# power.net
KiCad netlist of a schematic drawn in Altium Designer
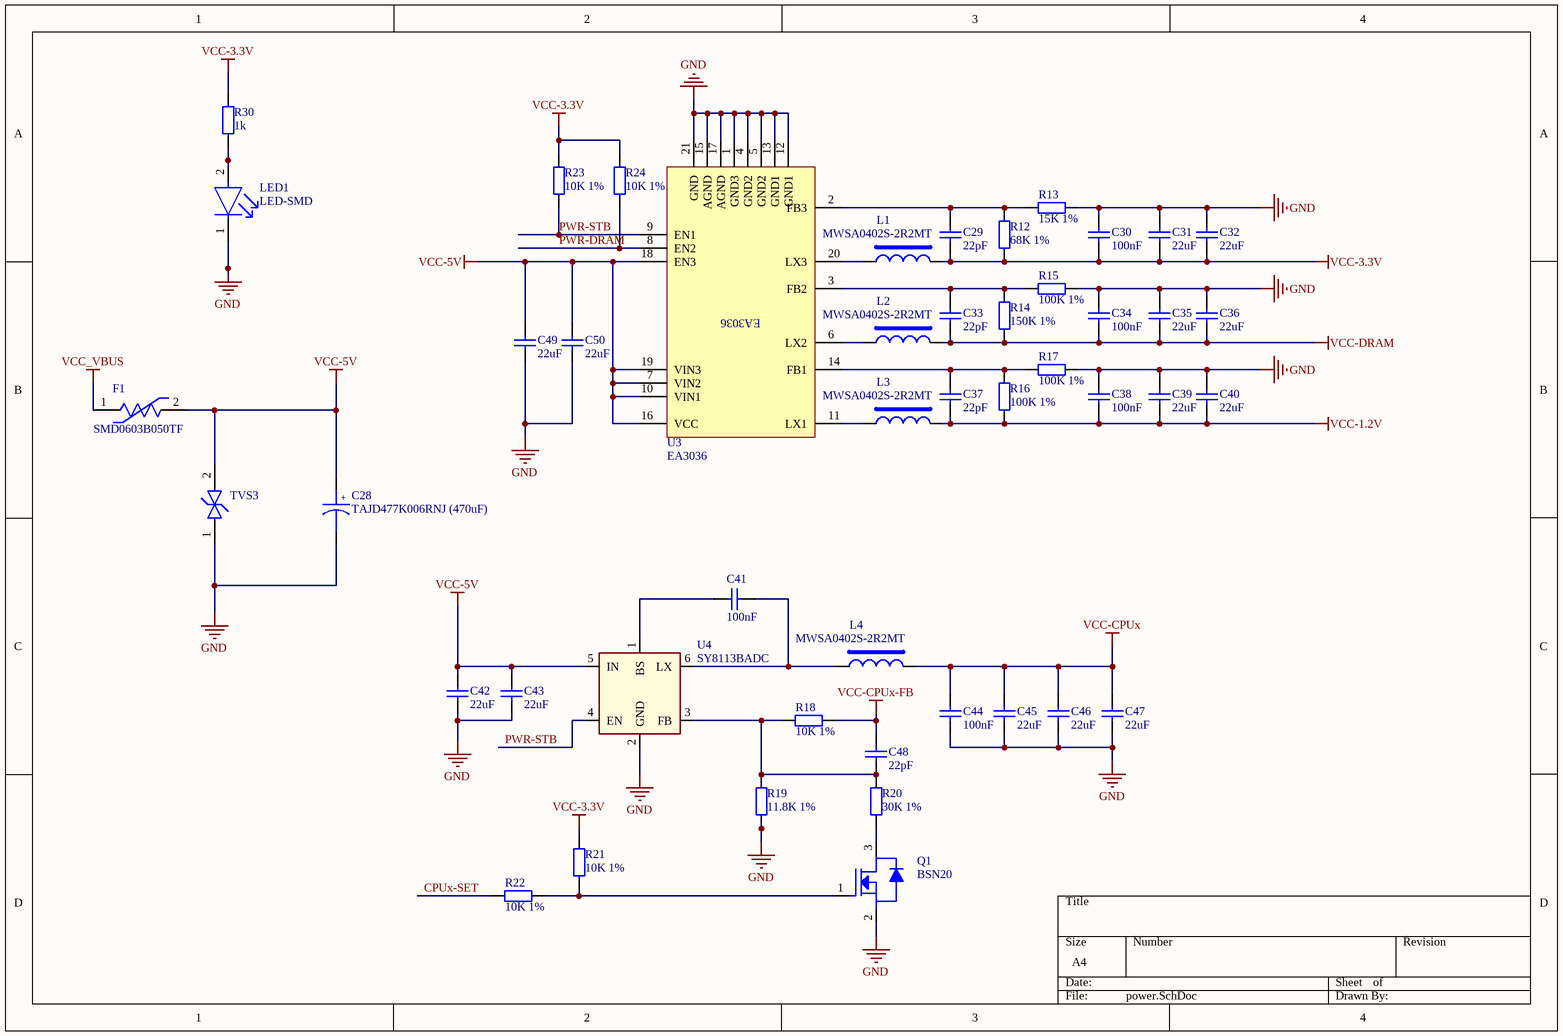
[diagram p0: power.SchDoc]

(export (version "E")
  (design (tool "Eeschema 10.0.6"))
  (components
    (comp (ref "C28")
      (value "TAJD477K006RNJ (470uF)")
      (footprint "7343_C_POL")
      (description "smd pol capacitor")
      (libsource (lib "Schlib") (part "CAP-POL-SMD"))
    )
    (comp (ref "C29")
      (value "22pF")
      (footprint "0402_C")
      (description "smd capacitor")
      (libsource (lib "Schlib") (part "CAP-SMD"))
    )
    (comp (ref "C30")
      (value "100nF")
      (footprint "0402_C")
      (description "smd capacitor")
      (libsource (lib "Schlib") (part "CAP-SMD"))
    )
    (comp (ref "C31")
      (value "22uF")
      (footprint "0603_C")
      (description "smd capacitor")
      (libsource (lib "Schlib") (part "CAP-SMD"))
    )
    (comp (ref "C32")
      (value "22uF")
      (footprint "0603_C")
      (description "smd capacitor")
      (libsource (lib "Schlib") (part "CAP-SMD"))
    )
    (comp (ref "C33")
      (value "22pF")
      (footprint "0402_C")
      (description "smd capacitor")
      (libsource (lib "Schlib") (part "CAP-SMD"))
    )
    (comp (ref "C34")
      (value "100nF")
      (footprint "0402_C")
      (description "smd capacitor")
      (libsource (lib "Schlib") (part "CAP-SMD"))
    )
    (comp (ref "C35")
      (value "22uF")
      (footprint "0603_C")
      (description "smd capacitor")
      (libsource (lib "Schlib") (part "CAP-SMD"))
    )
    (comp (ref "C36")
      (value "22uF")
      (footprint "0603_C")
      (description "smd capacitor")
      (libsource (lib "Schlib") (part "CAP-SMD"))
    )
    (comp (ref "C37")
      (value "22pF")
      (footprint "0402_C")
      (description "smd capacitor")
      (libsource (lib "Schlib") (part "CAP-SMD"))
    )
    (comp (ref "C38")
      (value "100nF")
      (footprint "0402_C")
      (description "smd capacitor")
      (libsource (lib "Schlib") (part "CAP-SMD"))
    )
    (comp (ref "C39")
      (value "22uF")
      (footprint "0603_C")
      (description "smd capacitor")
      (libsource (lib "Schlib") (part "CAP-SMD"))
    )
    (comp (ref "C40")
      (value "22uF")
      (footprint "0603_C")
      (description "smd capacitor")
      (libsource (lib "Schlib") (part "CAP-SMD"))
    )
    (comp (ref "C41")
      (value "100nF")
      (footprint "0402_C")
      (description "smd capacitor")
      (libsource (lib "Schlib") (part "CAP-SMD"))
    )
    (comp (ref "C42")
      (value "22uF")
      (footprint "0603_C")
      (description "smd capacitor")
      (libsource (lib "Schlib") (part "CAP-SMD"))
    )
    (comp (ref "C43")
      (value "22uF")
      (footprint "0603_C")
      (description "smd capacitor")
      (libsource (lib "Schlib") (part "CAP-SMD"))
    )
    (comp (ref "C44")
      (value "100nF")
      (footprint "0402_C")
      (description "smd capacitor")
      (libsource (lib "Schlib") (part "CAP-SMD"))
    )
    (comp (ref "C45")
      (value "22uF")
      (footprint "0603_C")
      (description "smd capacitor")
      (libsource (lib "Schlib") (part "CAP-SMD"))
    )
    (comp (ref "C46")
      (value "22uF")
      (footprint "0603_C")
      (description "smd capacitor")
      (libsource (lib "Schlib") (part "CAP-SMD"))
    )
    (comp (ref "C47")
      (value "22uF")
      (footprint "0603_C")
      (description "smd capacitor")
      (libsource (lib "Schlib") (part "CAP-SMD"))
    )
    (comp (ref "C48")
      (value "22pF")
      (footprint "0402_C")
      (description "smd capacitor")
      (libsource (lib "Schlib") (part "CAP-SMD"))
    )
    (comp (ref "C49")
      (value "22uF")
      (footprint "0603_C")
      (description "smd capacitor")
      (libsource (lib "Schlib") (part "CAP-SMD"))
    )
    (comp (ref "C50")
      (value "22uF")
      (footprint "0603_C")
      (description "smd capacitor")
      (libsource (lib "Schlib") (part "CAP-SMD"))
    )
    (comp (ref "F1")
      (value "SMD0603B050TF")
      (footprint "0603_FUSE")
      (description "RESET FUSE")
      (libsource (lib "Schlib") (part "FUSE-SMD"))
    )
    (comp (ref "L1")
      (value "MWSA0402S-2R2MT")
      (footprint "0402S_L")
      (description "inductor")
      (libsource (lib "Schlib") (part "IND-SMD"))
    )
    (comp (ref "L2")
      (value "MWSA0402S-2R2MT")
      (footprint "0402S_L")
      (description "inductor")
      (libsource (lib "Schlib") (part "IND-SMD"))
    )
    (comp (ref "L3")
      (value "MWSA0402S-2R2MT")
      (footprint "0402S_L")
      (description "inductor")
      (libsource (lib "Schlib") (part "IND-SMD"))
    )
    (comp (ref "L4")
      (value "MWSA0402S-2R2MT")
      (footprint "0402S_L")
      (description "inductor")
      (libsource (lib "Schlib") (part "IND-SMD"))
    )
    (comp (ref "LED1")
      (value "LED-SMD")
      (footprint "0603_LED_BLUE")
      (description "0603 LED SMD")
      (libsource (lib "Schlib") (part "LED-SMD"))
    )
    (comp (ref "Q1")
      (value "BSN20")
      (footprint "SOT-23")
      (description "nmos")
      (libsource (lib "Schlib") (part "NMOS"))
    )
    (comp (ref "R12")
      (value "68K 1%")
      (footprint "0402_R")
      (description "smd resistor")
      (libsource (lib "Schlib") (part "RES-SMD"))
    )
    (comp (ref "R13")
      (value "15K 1%")
      (footprint "0402_R")
      (description "smd resistor")
      (libsource (lib "") (part "RES-SMD_2"))
    )
    (comp (ref "R14")
      (value "150K 1%")
      (footprint "0402_R")
      (description "smd resistor")
      (libsource (lib "Schlib") (part "RES-SMD"))
    )
    (comp (ref "R15")
      (value "100K 1%")
      (footprint "0402_R")
      (description "smd resistor")
      (libsource (lib "") (part "RES-SMD_2"))
    )
    (comp (ref "R16")
      (value "100K 1%")
      (footprint "0402_R")
      (description "smd resistor")
      (libsource (lib "Schlib") (part "RES-SMD"))
    )
    (comp (ref "R17")
      (value "100K 1%")
      (footprint "0402_R")
      (description "smd resistor")
      (libsource (lib "") (part "RES-SMD_2"))
    )
    (comp (ref "R18")
      (value "10K 1%")
      (footprint "0402_R")
      (description "smd resistor")
      (libsource (lib "") (part "RES-SMD_1"))
    )
    (comp (ref "R19")
      (value "11.8K 1%")
      (footprint "0402_R")
      (description "smd resistor")
      (libsource (lib "Schlib") (part "RES-SMD"))
    )
    (comp (ref "R20")
      (value "30K 1%")
      (footprint "0402_R")
      (description "smd resistor")
      (libsource (lib "Schlib") (part "RES-SMD"))
    )
    (comp (ref "R21")
      (value "10K 1%")
      (footprint "0402_R")
      (description "smd resistor")
      (libsource (lib "Schlib") (part "RES-SMD"))
    )
    (comp (ref "R22")
      (value "10K 1%")
      (footprint "0402_R")
      (description "smd resistor")
      (libsource (lib "") (part "RES-SMD_2"))
    )
    (comp (ref "R23")
      (value "10K 1%")
      (footprint "0402_R")
      (description "smd resistor")
      (libsource (lib "Schlib") (part "RES-SMD"))
    )
    (comp (ref "R24")
      (value "10K 1%")
      (footprint "0402_R")
      (description "smd resistor")
      (libsource (lib "Schlib") (part "RES-SMD"))
    )
    (comp (ref "R30")
      (value "1k")
      (footprint "0402_R")
      (description "smd resistor")
      (libsource (lib "Schlib") (part "RES-SMD"))
    )
    (comp (ref "TVS3")
      (value "BSD5C051L")
      (footprint "SOD-523_TVS")
      (description "Transient Voltage Suppressor")
      (libsource (lib "Schlib") (part "TVS-DIODE-SMD"))
    )
    (comp (ref "U3")
      (value "EA3036")
      (footprint "QFN3x3-20")
      (description "DC-DC")
      (libsource (lib "Schlib") (part "EA3036"))
    )
    (comp (ref "U4")
      (value "SY8113BADC")
      (footprint "SOT23-6")
      (description "DC-DC")
      (libsource (lib "Schlib") (part "SY8113BADC"))
    )
  )
  (nets
    (net (code "1") (name "/CPUx-SET") (class "Default")
      (node (ref "R22") (pin "2") (pinfunction "2_2") (pintype "passive"))
    )
    (net (code "2") (name "/PWR-DRAM") (class "Default")
      (node (ref "R24") (pin "1") (pinfunction "1_1") (pintype "passive"))
      (node (ref "U3") (pin "8") (pinfunction "EN2_8") (pintype "passive"))
    )
    (net (code "3") (name "/PWR-STB") (class "Default")
      (node (ref "R23") (pin "1") (pinfunction "1_1") (pintype "passive"))
      (node (ref "U3") (pin "9") (pinfunction "EN1_9") (pintype "passive"))
      (node (ref "U4") (pin "4") (pinfunction "EN_4") (pintype "passive"))
    )
    (net (code "4") (name "GND") (class "Default")
      (node (ref "C28") (pin "2") (pinfunction "2_2") (pintype "passive"))
      (node (ref "C30") (pin "1") (pintype "passive"))
      (node (ref "C31") (pin "1") (pintype "passive"))
      (node (ref "C32") (pin "1") (pintype "passive"))
      (node (ref "C34") (pin "1") (pintype "passive"))
      (node (ref "C35") (pin "1") (pintype "passive"))
      (node (ref "C36") (pin "1") (pintype "passive"))
      (node (ref "C38") (pin "1") (pintype "passive"))
      (node (ref "C39") (pin "1") (pintype "passive"))
      (node (ref "C40") (pin "1") (pintype "passive"))
      (node (ref "C42") (pin "2") (pintype "passive"))
      (node (ref "C43") (pin "2") (pintype "passive"))
      (node (ref "C44") (pin "2") (pintype "passive"))
      (node (ref "C45") (pin "2") (pintype "passive"))
      (node (ref "C46") (pin "2") (pintype "passive"))
      (node (ref "C47") (pin "2") (pintype "passive"))
      (node (ref "C49") (pin "2") (pintype "passive"))
      (node (ref "C50") (pin "2") (pintype "passive"))
      (node (ref "LED1") (pin "1") (pinfunction "-_1") (pintype "passive"))
      (node (ref "Q1") (pin "2") (pinfunction "SOURCE_2") (pintype "passive"))
      (node (ref "R13") (pin "1") (pinfunction "1_1") (pintype "passive"))
      (node (ref "R15") (pin "1") (pinfunction "1_1") (pintype "passive"))
      (node (ref "R17") (pin "1") (pinfunction "1_1") (pintype "passive"))
      (node (ref "R19") (pin "1") (pinfunction "1_1") (pintype "passive"))
      (node (ref "TVS3") (pin "1") (pinfunction "1_1") (pintype "passive"))
      (node (ref "U3") (pin "1") (pinfunction "GND3_1") (pintype "passive"))
      (node (ref "U3") (pin "12") (pinfunction "GND1_12") (pintype "passive"))
      (node (ref "U3") (pin "13") (pinfunction "GND1_13") (pintype "passive"))
      (node (ref "U3") (pin "15") (pinfunction "AGND_15") (pintype "passive"))
      (node (ref "U3") (pin "17") (pinfunction "AGND_17") (pintype "passive"))
      (node (ref "U3") (pin "21") (pinfunction "GND_21") (pintype "passive"))
      (node (ref "U3") (pin "4") (pinfunction "GND2_4") (pintype "passive"))
      (node (ref "U3") (pin "5") (pinfunction "GND2_5") (pintype "passive"))
      (node (ref "U4") (pin "2") (pinfunction "GND_2") (pintype "passive"))
    )
    (net (code "5") (name "Net-(LED1-+)") (class "Default")
      (node (ref "LED1") (pin "2") (pinfunction "+_2") (pintype "passive"))
      (node (ref "R30") (pin "1") (pinfunction "1_1") (pintype "passive"))
    )
    (net (code "6") (name "Net-(Q1-DRAIN)") (class "Default")
      (node (ref "Q1") (pin "3") (pinfunction "DRAIN_3") (pintype "passive"))
      (node (ref "R20") (pin "1") (pinfunction "1_1") (pintype "passive"))
    )
    (net (code "7") (name "Net-(Q1-GATE)") (class "Default")
      (node (ref "Q1") (pin "1") (pinfunction "GATE_1") (pintype "passive"))
      (node (ref "R21") (pin "1") (pinfunction "1_1") (pintype "passive"))
      (node (ref "R22") (pin "1") (pinfunction "1_1") (pintype "passive"))
    )
    (net (code "8") (name "Net-(U3-FB1)") (class "Default")
      (node (ref "C37") (pin "1") (pintype "passive"))
      (node (ref "R16") (pin "2") (pinfunction "2_2") (pintype "passive"))
      (node (ref "R17") (pin "2") (pinfunction "2_2") (pintype "passive"))
      (node (ref "U3") (pin "14") (pinfunction "FB1_14") (pintype "passive"))
    )
    (net (code "9") (name "Net-(U3-FB2)") (class "Default")
      (node (ref "C33") (pin "1") (pintype "passive"))
      (node (ref "R14") (pin "2") (pinfunction "2_2") (pintype "passive"))
      (node (ref "R15") (pin "2") (pinfunction "2_2") (pintype "passive"))
      (node (ref "U3") (pin "3") (pinfunction "FB2_3") (pintype "passive"))
    )
    (net (code "10") (name "Net-(U3-FB3)") (class "Default")
      (node (ref "C29") (pin "1") (pintype "passive"))
      (node (ref "R12") (pin "2") (pinfunction "2_2") (pintype "passive"))
      (node (ref "R13") (pin "2") (pinfunction "2_2") (pintype "passive"))
      (node (ref "U3") (pin "2") (pinfunction "FB3_2") (pintype "passive"))
    )
    (net (code "11") (name "Net-(U3-LX1)") (class "Default")
      (node (ref "L3") (pin "1") (pinfunction "1_1") (pintype "passive"))
      (node (ref "U3") (pin "11") (pinfunction "LX1_11") (pintype "passive"))
    )
    (net (code "12") (name "Net-(U3-LX2)") (class "Default")
      (node (ref "L2") (pin "1") (pinfunction "1_1") (pintype "passive"))
      (node (ref "U3") (pin "6") (pinfunction "LX2_6") (pintype "passive"))
    )
    (net (code "13") (name "Net-(U3-LX3)") (class "Default")
      (node (ref "L1") (pin "1") (pinfunction "1_1") (pintype "passive"))
      (node (ref "U3") (pin "20") (pinfunction "LX3_20") (pintype "passive"))
    )
    (net (code "14") (name "Net-(U4-BS)") (class "Default")
      (node (ref "C41") (pin "1") (pintype "passive"))
      (node (ref "U4") (pin "1") (pinfunction "BS_1") (pintype "passive"))
    )
    (net (code "15") (name "Net-(U4-FB)") (class "Default")
      (node (ref "C48") (pin "2") (pintype "passive"))
      (node (ref "R18") (pin "1") (pinfunction "1_1") (pintype "passive"))
      (node (ref "R19") (pin "2") (pinfunction "2_2") (pintype "passive"))
      (node (ref "R20") (pin "2") (pinfunction "2_2") (pintype "passive"))
      (node (ref "U4") (pin "3") (pinfunction "FB_3") (pintype "passive"))
    )
    (net (code "16") (name "Net-(U4-LX)") (class "Default")
      (node (ref "C41") (pin "2") (pintype "passive"))
      (node (ref "L4") (pin "1") (pinfunction "1_1") (pintype "passive"))
      (node (ref "U4") (pin "6") (pinfunction "LX_6") (pintype "passive"))
    )
    (net (code "17") (name "VCC-1.2V") (class "Default")
      (node (ref "C37") (pin "2") (pintype "passive"))
      (node (ref "C38") (pin "2") (pintype "passive"))
      (node (ref "C39") (pin "2") (pintype "passive"))
      (node (ref "C40") (pin "2") (pintype "passive"))
      (node (ref "L3") (pin "2") (pinfunction "2_2") (pintype "passive"))
      (node (ref "R16") (pin "1") (pinfunction "1_1") (pintype "passive"))
    )
    (net (code "18") (name "VCC-3.3V") (class "Default")
      (node (ref "C29") (pin "2") (pintype "passive"))
      (node (ref "C30") (pin "2") (pintype "passive"))
      (node (ref "C31") (pin "2") (pintype "passive"))
      (node (ref "C32") (pin "2") (pintype "passive"))
      (node (ref "L1") (pin "2") (pinfunction "2_2") (pintype "passive"))
      (node (ref "R12") (pin "1") (pinfunction "1_1") (pintype "passive"))
      (node (ref "R21") (pin "2") (pinfunction "2_2") (pintype "passive"))
      (node (ref "R23") (pin "2") (pinfunction "2_2") (pintype "passive"))
      (node (ref "R24") (pin "2") (pinfunction "2_2") (pintype "passive"))
      (node (ref "R30") (pin "2") (pinfunction "2_2") (pintype "passive"))
    )
    (net (code "19") (name "VCC-5V") (class "Default")
      (node (ref "C28") (pin "1") (pinfunction "1_1") (pintype "passive"))
      (node (ref "C42") (pin "1") (pintype "passive"))
      (node (ref "C43") (pin "1") (pintype "passive"))
      (node (ref "C49") (pin "1") (pintype "passive"))
      (node (ref "C50") (pin "1") (pintype "passive"))
      (node (ref "F1") (pin "2") (pintype "passive"))
      (node (ref "TVS3") (pin "2") (pinfunction "2_2") (pintype "passive"))
      (node (ref "U3") (pin "10") (pinfunction "VIN1_10") (pintype "passive"))
      (node (ref "U3") (pin "16") (pinfunction "VCC_16") (pintype "passive"))
      (node (ref "U3") (pin "18") (pinfunction "EN3_18") (pintype "passive"))
      (node (ref "U3") (pin "19") (pinfunction "VIN3_19") (pintype "passive"))
      (node (ref "U3") (pin "7") (pinfunction "VIN2_7") (pintype "passive"))
      (node (ref "U4") (pin "5") (pinfunction "IN_5") (pintype "passive"))
    )
    (net (code "20") (name "VCC-CPUx") (class "Default")
      (node (ref "C44") (pin "1") (pintype "passive"))
      (node (ref "C45") (pin "1") (pintype "passive"))
      (node (ref "C46") (pin "1") (pintype "passive"))
      (node (ref "C47") (pin "1") (pintype "passive"))
      (node (ref "L4") (pin "2") (pinfunction "2_2") (pintype "passive"))
    )
    (net (code "21") (name "VCC-CPUx-FB") (class "Default")
      (node (ref "C48") (pin "1") (pintype "passive"))
      (node (ref "R18") (pin "2") (pinfunction "2_2") (pintype "passive"))
    )
    (net (code "22") (name "VCC-DRAM") (class "Default")
      (node (ref "C33") (pin "2") (pintype "passive"))
      (node (ref "C34") (pin "2") (pintype "passive"))
      (node (ref "C35") (pin "2") (pintype "passive"))
      (node (ref "C36") (pin "2") (pintype "passive"))
      (node (ref "L2") (pin "2") (pinfunction "2_2") (pintype "passive"))
      (node (ref "R14") (pin "1") (pinfunction "1_1") (pintype "passive"))
    )
    (net (code "23") (name "VCC_VBUS") (class "Default") (node (ref "F1") (pin "1") (pintype "passive")))
  )
)
